# eMMC.net
KiCad netlist of a schematic drawn in Altium Designer
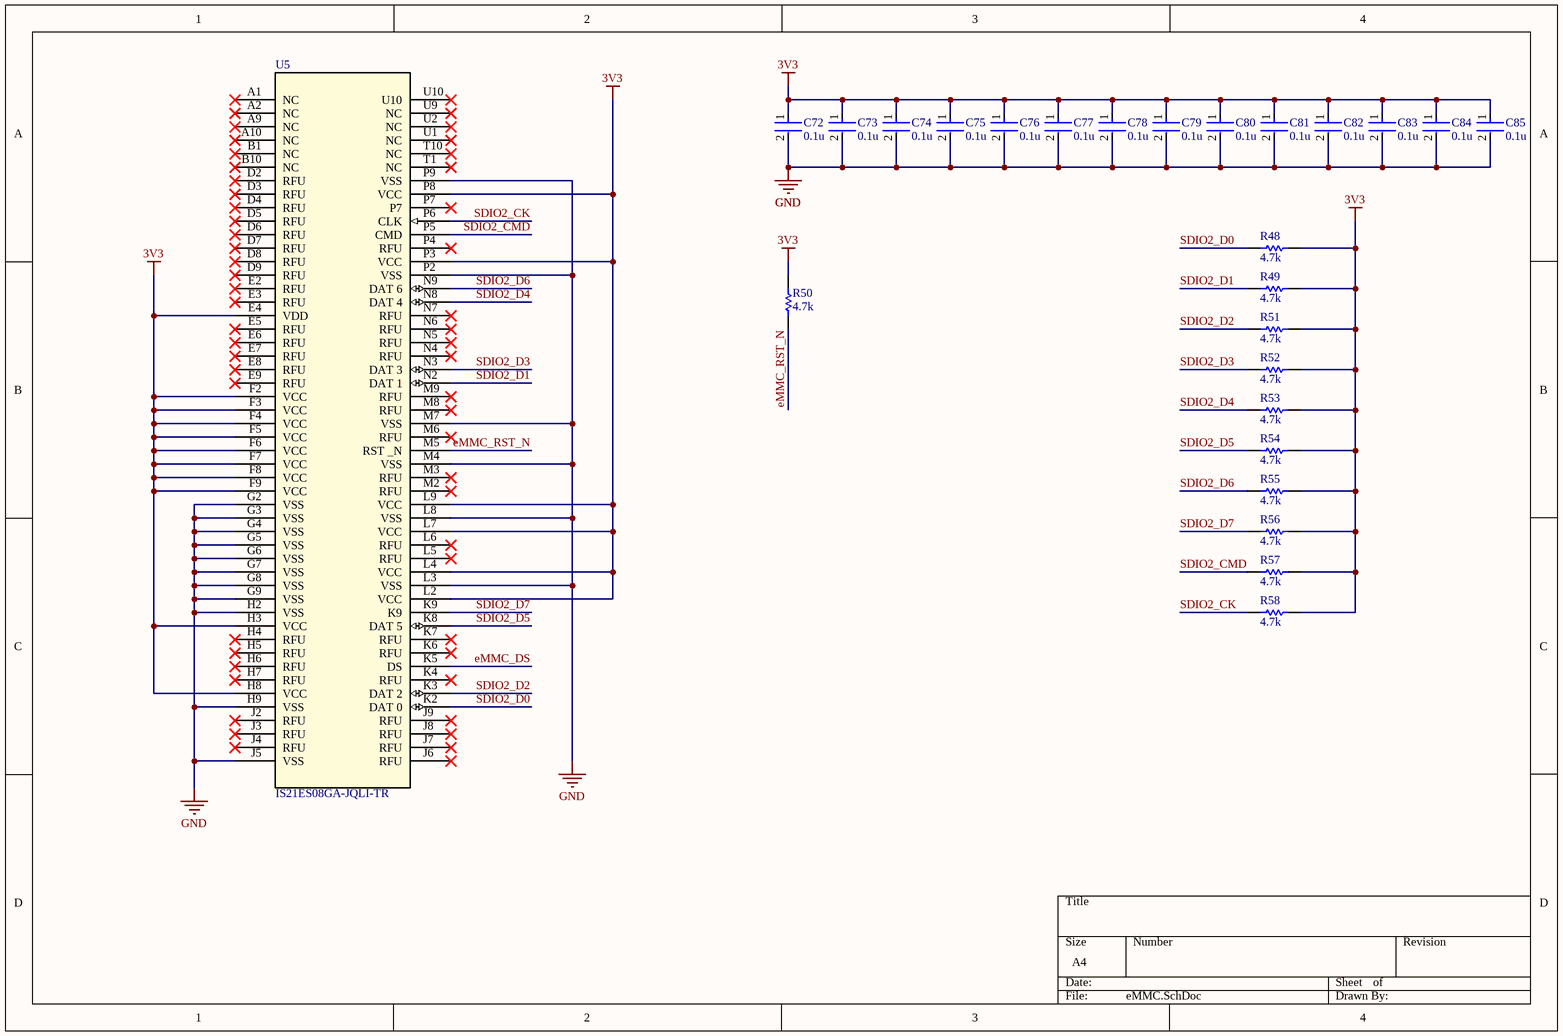
[diagram p0: eMMC.SchDoc]

(export (version "E")
  (design (tool "Eeschema 10.0.6"))
  (components
    (comp (ref "C72")
      (value "0.1u")
      (footprint "FP-C0603C-CF-MFG")
      (description "CAP CER 0.1UF 50V X7R 0603")
      (fields (field (name "TOLERANCE") "0.1") (field (name "MANUFACTURER") "KEMET"))
      (libsource (lib "Altium Content Vault") (part "b4654b650e69147ec39a6b967a45e02"))
    )
    (comp (ref "C73")
      (value "0.1u")
      (footprint "FP-C0603C-CF-MFG")
      (description "CAP CER 0.1UF 50V X7R 0603")
      (fields (field (name "TOLERANCE") "0.1") (field (name "MANUFACTURER") "KEMET"))
      (libsource (lib "Altium Content Vault") (part "b4654b650e69147ec39a6b967a45e02"))
    )
    (comp (ref "C74")
      (value "0.1u")
      (footprint "FP-C0603C-CF-MFG")
      (description "CAP CER 0.1UF 50V X7R 0603")
      (fields (field (name "TOLERANCE") "0.1") (field (name "MANUFACTURER") "KEMET"))
      (libsource (lib "Altium Content Vault") (part "b4654b650e69147ec39a6b967a45e02"))
    )
    (comp (ref "C75")
      (value "0.1u")
      (footprint "FP-C0603C-CF-MFG")
      (description "CAP CER 0.1UF 50V X7R 0603")
      (fields (field (name "TOLERANCE") "0.1") (field (name "MANUFACTURER") "KEMET"))
      (libsource (lib "Altium Content Vault") (part "b4654b650e69147ec39a6b967a45e02"))
    )
    (comp (ref "C76")
      (value "0.1u")
      (footprint "FP-C0603C-CF-MFG")
      (description "CAP CER 0.1UF 50V X7R 0603")
      (fields (field (name "TOLERANCE") "0.1") (field (name "MANUFACTURER") "KEMET"))
      (libsource (lib "Altium Content Vault") (part "b4654b650e69147ec39a6b967a45e02"))
    )
    (comp (ref "C77")
      (value "0.1u")
      (footprint "FP-C0603C-CF-MFG")
      (description "CAP CER 0.1UF 50V X7R 0603")
      (fields (field (name "TOLERANCE") "0.1") (field (name "MANUFACTURER") "KEMET"))
      (libsource (lib "Altium Content Vault") (part "b4654b650e69147ec39a6b967a45e02"))
    )
    (comp (ref "C78")
      (value "0.1u")
      (footprint "FP-C0603C-CF-MFG")
      (description "CAP CER 0.1UF 50V X7R 0603")
      (fields (field (name "TOLERANCE") "0.1") (field (name "MANUFACTURER") "KEMET"))
      (libsource (lib "Altium Content Vault") (part "b4654b650e69147ec39a6b967a45e02"))
    )
    (comp (ref "C79")
      (value "0.1u")
      (footprint "FP-C0603C-CF-MFG")
      (description "CAP CER 0.1UF 50V X7R 0603")
      (fields (field (name "TOLERANCE") "0.1") (field (name "MANUFACTURER") "KEMET"))
      (libsource (lib "Altium Content Vault") (part "b4654b650e69147ec39a6b967a45e02"))
    )
    (comp (ref "C80")
      (value "0.1u")
      (footprint "FP-C0603C-CF-MFG")
      (description "CAP CER 0.1UF 50V X7R 0603")
      (fields (field (name "TOLERANCE") "0.1") (field (name "MANUFACTURER") "KEMET"))
      (libsource (lib "Altium Content Vault") (part "b4654b650e69147ec39a6b967a45e02"))
    )
    (comp (ref "C81")
      (value "0.1u")
      (footprint "FP-C0603C-CF-MFG")
      (description "CAP CER 0.1UF 50V X7R 0603")
      (fields (field (name "TOLERANCE") "0.1") (field (name "MANUFACTURER") "KEMET"))
      (libsource (lib "Altium Content Vault") (part "b4654b650e69147ec39a6b967a45e02"))
    )
    (comp (ref "C82")
      (value "0.1u")
      (footprint "FP-C0603C-CF-MFG")
      (description "CAP CER 0.1UF 50V X7R 0603")
      (fields (field (name "TOLERANCE") "0.1") (field (name "MANUFACTURER") "KEMET"))
      (libsource (lib "Altium Content Vault") (part "b4654b650e69147ec39a6b967a45e02"))
    )
    (comp (ref "C83")
      (value "0.1u")
      (footprint "FP-C0603C-CF-MFG")
      (description "CAP CER 0.1UF 50V X7R 0603")
      (fields (field (name "TOLERANCE") "0.1") (field (name "MANUFACTURER") "KEMET"))
      (libsource (lib "Altium Content Vault") (part "b4654b650e69147ec39a6b967a45e02"))
    )
    (comp (ref "C84")
      (value "0.1u")
      (footprint "FP-C0603C-CF-MFG")
      (description "CAP CER 0.1UF 50V X7R 0603")
      (fields (field (name "TOLERANCE") "0.1") (field (name "MANUFACTURER") "KEMET"))
      (libsource (lib "Altium Content Vault") (part "b4654b650e69147ec39a6b967a45e02"))
    )
    (comp (ref "C85")
      (value "0.1u")
      (footprint "FP-C0603C-CF-MFG")
      (description "CAP CER 0.1UF 50V X7R 0603")
      (fields (field (name "TOLERANCE") "0.1") (field (name "MANUFACTURER") "KEMET"))
      (libsource (lib "Altium Content Vault") (part "b4654b650e69147ec39a6b967a45e02"))
    )
    (comp (ref "R48")
      (value "4.7k")
      (footprint "RESC1609X50X30NL8T20")
      (description "Chip Resistor, 10 KOhm, +/- 1%, 100 mW, -55 to 155 degC, 0603 (1608 Metric), RoHS, Tape and Reel")
      (fields (field (name "MANUFACTURER") "Vishay Semiconductor"))
      (libsource (lib "Altium Content Vault") (part "RES-2"))
    )
    (comp (ref "R49")
      (value "4.7k")
      (footprint "RESC1609X50X30NL8T20")
      (description "Chip Resistor, 10 KOhm, +/- 1%, 100 mW, -55 to 155 degC, 0603 (1608 Metric), RoHS, Tape and Reel")
      (fields (field (name "MANUFACTURER") "Vishay Semiconductor"))
      (libsource (lib "Altium Content Vault") (part "RES-2"))
    )
    (comp (ref "R50")
      (value "4.7k")
      (footprint "RESC1609X50X30NL8T20")
      (description "Chip Resistor, 10 KOhm, +/- 1%, 100 mW, -55 to 155 degC, 0603 (1608 Metric), RoHS, Tape and Reel")
      (fields (field (name "MANUFACTURER") "Vishay Semiconductor"))
      (libsource (lib "Altium Content Vault") (part "RES-2"))
    )
    (comp (ref "R51")
      (value "4.7k")
      (footprint "RESC1609X50X30NL8T20")
      (description "Chip Resistor, 10 KOhm, +/- 1%, 100 mW, -55 to 155 degC, 0603 (1608 Metric), RoHS, Tape and Reel")
      (fields (field (name "MANUFACTURER") "Vishay Semiconductor"))
      (libsource (lib "Altium Content Vault") (part "RES-2"))
    )
    (comp (ref "R52")
      (value "4.7k")
      (footprint "RESC1609X50X30NL8T20")
      (description "Chip Resistor, 10 KOhm, +/- 1%, 100 mW, -55 to 155 degC, 0603 (1608 Metric), RoHS, Tape and Reel")
      (fields (field (name "MANUFACTURER") "Vishay Semiconductor"))
      (libsource (lib "Altium Content Vault") (part "RES-2"))
    )
    (comp (ref "R53")
      (value "4.7k")
      (footprint "RESC1609X50X30NL8T20")
      (description "Chip Resistor, 10 KOhm, +/- 1%, 100 mW, -55 to 155 degC, 0603 (1608 Metric), RoHS, Tape and Reel")
      (fields (field (name "MANUFACTURER") "Vishay Semiconductor"))
      (libsource (lib "Altium Content Vault") (part "RES-2"))
    )
    (comp (ref "R54")
      (value "4.7k")
      (footprint "RESC1609X50X30NL8T20")
      (description "Chip Resistor, 10 KOhm, +/- 1%, 100 mW, -55 to 155 degC, 0603 (1608 Metric), RoHS, Tape and Reel")
      (fields (field (name "MANUFACTURER") "Vishay Semiconductor"))
      (libsource (lib "Altium Content Vault") (part "RES-2"))
    )
    (comp (ref "R55")
      (value "4.7k")
      (footprint "RESC1609X50X30NL8T20")
      (description "Chip Resistor, 10 KOhm, +/- 1%, 100 mW, -55 to 155 degC, 0603 (1608 Metric), RoHS, Tape and Reel")
      (fields (field (name "MANUFACTURER") "Vishay Semiconductor"))
      (libsource (lib "Altium Content Vault") (part "RES-2"))
    )
    (comp (ref "R56")
      (value "4.7k")
      (footprint "RESC1609X50X30NL8T20")
      (description "Chip Resistor, 10 KOhm, +/- 1%, 100 mW, -55 to 155 degC, 0603 (1608 Metric), RoHS, Tape and Reel")
      (fields (field (name "MANUFACTURER") "Vishay Semiconductor"))
      (libsource (lib "Altium Content Vault") (part "RES-2"))
    )
    (comp (ref "R57")
      (value "4.7k")
      (footprint "RESC1609X50X30NL8T20")
      (description "Chip Resistor, 10 KOhm, +/- 1%, 100 mW, -55 to 155 degC, 0603 (1608 Metric), RoHS, Tape and Reel")
      (fields (field (name "MANUFACTURER") "Vishay Semiconductor"))
      (libsource (lib "Altium Content Vault") (part "RES-2"))
    )
    (comp (ref "R58")
      (value "4.7k")
      (footprint "RESC1609X50X30NL8T20")
      (description "Chip Resistor, 10 KOhm, +/- 1%, 100 mW, -55 to 155 degC, 0603 (1608 Metric), RoHS, Tape and Reel")
      (fields (field (name "MANUFACTURER") "Vishay Semiconductor"))
      (libsource (lib "Altium Content Vault") (part "RES-2"))
    )
    (comp (ref "U5")
      (value "IS21ES08GA-JQLI-TR")
      (footprint "FBGA100_ISI")
      (description "No Description Available")
      (libsource (lib "Master") (part "IS21ES08GA-JQLI-TR"))
    )
  )
  (nets
    (net (code "1") (name "/SDIO2_CK") (class "Default")
      (node (ref "R58") (pin "2") (pinfunction "2_2") (pintype "passive"))
      (node (ref "U5") (pin "P6") (pinfunction "CLK_P6") (pintype "input"))
    )
    (net (code "2") (name "/SDIO2_CMD") (class "Default")
      (node (ref "R57") (pin "2") (pinfunction "2_2") (pintype "passive"))
      (node (ref "U5") (pin "P5") (pinfunction "CMD_P5") (pintype "passive"))
    )
    (net (code "3") (name "/SDIO2_D0") (class "Default")
      (node (ref "R48") (pin "2") (pinfunction "2_2") (pintype "passive"))
      (node (ref "U5") (pin "K2") (pinfunction "DAT_0_K2") (pintype "bidirectional"))
    )
    (net (code "4") (name "/SDIO2_D1") (class "Default")
      (node (ref "R49") (pin "2") (pinfunction "2_2") (pintype "passive"))
      (node (ref "U5") (pin "N2") (pinfunction "DAT_1_N2") (pintype "bidirectional"))
    )
    (net (code "5") (name "/SDIO2_D2") (class "Default")
      (node (ref "R51") (pin "2") (pinfunction "2_2") (pintype "passive"))
      (node (ref "U5") (pin "K3") (pinfunction "DAT_2_K3") (pintype "bidirectional"))
    )
    (net (code "6") (name "/SDIO2_D3") (class "Default")
      (node (ref "R52") (pin "2") (pinfunction "2_2") (pintype "passive"))
      (node (ref "U5") (pin "N3") (pinfunction "DAT_3_N3") (pintype "bidirectional"))
    )
    (net (code "7") (name "/SDIO2_D4") (class "Default")
      (node (ref "R53") (pin "2") (pinfunction "2_2") (pintype "passive"))
      (node (ref "U5") (pin "N8") (pinfunction "DAT_4_N8") (pintype "bidirectional"))
    )
    (net (code "8") (name "/SDIO2_D5") (class "Default")
      (node (ref "R54") (pin "2") (pinfunction "2_2") (pintype "passive"))
      (node (ref "U5") (pin "K8") (pinfunction "DAT_5_K8") (pintype "bidirectional"))
    )
    (net (code "9") (name "/SDIO2_D6") (class "Default")
      (node (ref "R55") (pin "2") (pinfunction "2_2") (pintype "passive"))
      (node (ref "U5") (pin "N9") (pinfunction "DAT_6_N9") (pintype "bidirectional"))
    )
    (net (code "10") (name "/SDIO2_D7") (class "Default")
      (node (ref "R56") (pin "2") (pinfunction "2_2") (pintype "passive"))
      (node (ref "U5") (pin "K9") (pinfunction "K9_K9") (pintype "passive"))
    )
    (net (code "11") (name "/eMMC_DS") (class "Default")
      (node (ref "U5") (pin "K5") (pinfunction "DS_K5") (pintype "passive"))
    )
    (net (code "12") (name "/eMMC_RST_N") (class "Default")
      (node (ref "R50") (pin "1") (pinfunction "1_1") (pintype "passive"))
      (node (ref "U5") (pin "M5") (pinfunction "RST__N_M5") (pintype "passive"))
    )
    (net (code "13") (name "3V3") (class "Default")
      (node (ref "C72") (pin "1") (pinfunction "1_1") (pintype "passive"))
      (node (ref "C73") (pin "1") (pinfunction "1_1") (pintype "passive"))
      (node (ref "C74") (pin "1") (pinfunction "1_1") (pintype "passive"))
      (node (ref "C75") (pin "1") (pinfunction "1_1") (pintype "passive"))
      (node (ref "C76") (pin "1") (pinfunction "1_1") (pintype "passive"))
      (node (ref "C77") (pin "1") (pinfunction "1_1") (pintype "passive"))
      (node (ref "C78") (pin "1") (pinfunction "1_1") (pintype "passive"))
      (node (ref "C79") (pin "1") (pinfunction "1_1") (pintype "passive"))
      (node (ref "C80") (pin "1") (pinfunction "1_1") (pintype "passive"))
      (node (ref "C81") (pin "1") (pinfunction "1_1") (pintype "passive"))
      (node (ref "C82") (pin "1") (pinfunction "1_1") (pintype "passive"))
      (node (ref "C83") (pin "1") (pinfunction "1_1") (pintype "passive"))
      (node (ref "C84") (pin "1") (pinfunction "1_1") (pintype "passive"))
      (node (ref "C85") (pin "1") (pinfunction "1_1") (pintype "passive"))
      (node (ref "R48") (pin "1") (pinfunction "1_1") (pintype "passive"))
      (node (ref "R49") (pin "1") (pinfunction "1_1") (pintype "passive"))
      (node (ref "R50") (pin "2") (pinfunction "2_2") (pintype "passive"))
      (node (ref "R51") (pin "1") (pinfunction "1_1") (pintype "passive"))
      (node (ref "R52") (pin "1") (pinfunction "1_1") (pintype "passive"))
      (node (ref "R53") (pin "1") (pinfunction "1_1") (pintype "passive"))
      (node (ref "R54") (pin "1") (pinfunction "1_1") (pintype "passive"))
      (node (ref "R55") (pin "1") (pinfunction "1_1") (pintype "passive"))
      (node (ref "R56") (pin "1") (pinfunction "1_1") (pintype "passive"))
      (node (ref "R57") (pin "1") (pinfunction "1_1") (pintype "passive"))
      (node (ref "R58") (pin "1") (pinfunction "1_1") (pintype "passive"))
      (node (ref "U5") (pin "E4") (pinfunction "VDD_E4") (pintype "power_in"))
      (node (ref "U5") (pin "F2") (pinfunction "VCC_F2") (pintype "power_in"))
      (node (ref "U5") (pin "F3") (pinfunction "VCC_F3") (pintype "power_in"))
      (node (ref "U5") (pin "F4") (pinfunction "VCC_F4") (pintype "power_in"))
      (node (ref "U5") (pin "F5") (pinfunction "VCC_F5") (pintype "power_in"))
      (node (ref "U5") (pin "F6") (pinfunction "VCC_F6") (pintype "power_in"))
      (node (ref "U5") (pin "F7") (pinfunction "VCC_F7") (pintype "power_in"))
      (node (ref "U5") (pin "F8") (pinfunction "VCC_F8") (pintype "power_in"))
      (node (ref "U5") (pin "F9") (pinfunction "VCC_F9") (pintype "power_in"))
      (node (ref "U5") (pin "H3") (pinfunction "VCC_H3") (pintype "power_in"))
      (node (ref "U5") (pin "H8") (pinfunction "VCC_H8") (pintype "power_in"))
      (node (ref "U5") (pin "L2") (pinfunction "VCC_L2") (pintype "power_in"))
      (node (ref "U5") (pin "L4") (pinfunction "VCC_L4") (pintype "power_in"))
      (node (ref "U5") (pin "L7") (pinfunction "VCC_L7") (pintype "power_in"))
      (node (ref "U5") (pin "L9") (pinfunction "VCC_L9") (pintype "power_in"))
      (node (ref "U5") (pin "P3") (pinfunction "VCC_P3") (pintype "power_in"))
      (node (ref "U5") (pin "P8") (pinfunction "VCC_P8") (pintype "power_in"))
    )
    (net (code "14") (name "GND") (class "Default")
      (node (ref "C72") (pin "2") (pinfunction "2_2") (pintype "passive"))
      (node (ref "C73") (pin "2") (pinfunction "2_2") (pintype "passive"))
      (node (ref "C74") (pin "2") (pinfunction "2_2") (pintype "passive"))
      (node (ref "C75") (pin "2") (pinfunction "2_2") (pintype "passive"))
      (node (ref "C76") (pin "2") (pinfunction "2_2") (pintype "passive"))
      (node (ref "C77") (pin "2") (pinfunction "2_2") (pintype "passive"))
      (node (ref "C78") (pin "2") (pinfunction "2_2") (pintype "passive"))
      (node (ref "C79") (pin "2") (pinfunction "2_2") (pintype "passive"))
      (node (ref "C80") (pin "2") (pinfunction "2_2") (pintype "passive"))
      (node (ref "C81") (pin "2") (pinfunction "2_2") (pintype "passive"))
      (node (ref "C82") (pin "2") (pinfunction "2_2") (pintype "passive"))
      (node (ref "C83") (pin "2") (pinfunction "2_2") (pintype "passive"))
      (node (ref "C84") (pin "2") (pinfunction "2_2") (pintype "passive"))
      (node (ref "C85") (pin "2") (pinfunction "2_2") (pintype "passive"))
      (node (ref "U5") (pin "G2") (pinfunction "VSS_G2") (pintype "power_in"))
      (node (ref "U5") (pin "G3") (pinfunction "VSS_G3") (pintype "power_in"))
      (node (ref "U5") (pin "G4") (pinfunction "VSS_G4") (pintype "power_in"))
      (node (ref "U5") (pin "G5") (pinfunction "VSS_G5") (pintype "power_in"))
      (node (ref "U5") (pin "G6") (pinfunction "VSS_G6") (pintype "power_in"))
      (node (ref "U5") (pin "G7") (pinfunction "VSS_G7") (pintype "power_in"))
      (node (ref "U5") (pin "G8") (pinfunction "VSS_G8") (pintype "power_in"))
      (node (ref "U5") (pin "G9") (pinfunction "VSS_G9") (pintype "power_in"))
      (node (ref "U5") (pin "H2") (pinfunction "VSS_H2") (pintype "power_in"))
      (node (ref "U5") (pin "H9") (pinfunction "VSS_H9") (pintype "power_in"))
      (node (ref "U5") (pin "J5") (pinfunction "VSS_J5") (pintype "power_in"))
      (node (ref "U5") (pin "L3") (pinfunction "VSS_L3") (pintype "power_in"))
      (node (ref "U5") (pin "L8") (pinfunction "VSS_L8") (pintype "power_in"))
      (node (ref "U5") (pin "M4") (pinfunction "VSS_M4") (pintype "power_in"))
      (node (ref "U5") (pin "M7") (pinfunction "VSS_M7") (pintype "power_in"))
      (node (ref "U5") (pin "P2") (pinfunction "VSS_P2") (pintype "power_in"))
      (node (ref "U5") (pin "P9") (pinfunction "VSS_P9") (pintype "power_in"))
    )
    (net (code "15") (name "unconnected-(U5-NC-PadA1)") (class "Default")
      (node (ref "U5") (pin "A1") (pinfunction "NC_A1") (pintype "passive+no_connect"))
    )
    (net (code "16") (name "unconnected-(U5-NC-PadA2)") (class "Default")
      (node (ref "U5") (pin "A2") (pinfunction "NC_A2") (pintype "passive+no_connect"))
    )
    (net (code "17") (name "unconnected-(U5-NC-PadA9)") (class "Default")
      (node (ref "U5") (pin "A9") (pinfunction "NC_A9") (pintype "passive+no_connect"))
    )
    (net (code "18") (name "unconnected-(U5-NC-PadA10)") (class "Default")
      (node (ref "U5") (pin "A10") (pinfunction "NC_A10") (pintype "passive+no_connect"))
    )
    (net (code "19") (name "unconnected-(U5-NC-PadB1)") (class "Default")
      (node (ref "U5") (pin "B1") (pinfunction "NC_B1") (pintype "passive+no_connect"))
    )
    (net (code "20") (name "unconnected-(U5-NC-PadB10)") (class "Default")
      (node (ref "U5") (pin "B10") (pinfunction "NC_B10") (pintype "passive+no_connect"))
    )
    (net (code "21") (name "unconnected-(U5-NC-PadT1)") (class "Default")
      (node (ref "U5") (pin "T1") (pinfunction "NC_T1") (pintype "passive+no_connect"))
    )
    (net (code "22") (name "unconnected-(U5-NC-PadT10)") (class "Default")
      (node (ref "U5") (pin "T10") (pinfunction "NC_T10") (pintype "passive+no_connect"))
    )
    (net (code "23") (name "unconnected-(U5-NC-PadU1)") (class "Default")
      (node (ref "U5") (pin "U1") (pinfunction "NC_U1") (pintype "passive+no_connect"))
    )
    (net (code "24") (name "unconnected-(U5-NC-PadU2)") (class "Default")
      (node (ref "U5") (pin "U2") (pinfunction "NC_U2") (pintype "passive+no_connect"))
    )
    (net (code "25") (name "unconnected-(U5-NC-PadU9)") (class "Default")
      (node (ref "U5") (pin "U9") (pinfunction "NC_U9") (pintype "passive+no_connect"))
    )
    (net (code "26") (name "unconnected-(U5-PadP7)") (class "Default")
      (node (ref "U5") (pin "P7") (pinfunction "P7_P7") (pintype "passive+no_connect"))
    )
    (net (code "27") (name "unconnected-(U5-PadU10)") (class "Default")
      (node (ref "U5") (pin "U10") (pinfunction "U10_U10") (pintype "passive+no_connect"))
    )
    (net (code "28") (name "unconnected-(U5-RFU-PadD2)") (class "Default")
      (node (ref "U5") (pin "D2") (pinfunction "RFU_D2") (pintype "passive+no_connect"))
    )
    (net (code "29") (name "unconnected-(U5-RFU-PadD3)") (class "Default")
      (node (ref "U5") (pin "D3") (pinfunction "RFU_D3") (pintype "passive+no_connect"))
    )
    (net (code "30") (name "unconnected-(U5-RFU-PadD4)") (class "Default")
      (node (ref "U5") (pin "D4") (pinfunction "RFU_D4") (pintype "passive+no_connect"))
    )
    (net (code "31") (name "unconnected-(U5-RFU-PadD5)") (class "Default")
      (node (ref "U5") (pin "D5") (pinfunction "RFU_D5") (pintype "passive+no_connect"))
    )
    (net (code "32") (name "unconnected-(U5-RFU-PadD6)") (class "Default")
      (node (ref "U5") (pin "D6") (pinfunction "RFU_D6") (pintype "passive+no_connect"))
    )
    (net (code "33") (name "unconnected-(U5-RFU-PadD7)") (class "Default")
      (node (ref "U5") (pin "D7") (pinfunction "RFU_D7") (pintype "passive+no_connect"))
    )
    (net (code "34") (name "unconnected-(U5-RFU-PadD8)") (class "Default")
      (node (ref "U5") (pin "D8") (pinfunction "RFU_D8") (pintype "passive+no_connect"))
    )
    (net (code "35") (name "unconnected-(U5-RFU-PadD9)") (class "Default")
      (node (ref "U5") (pin "D9") (pinfunction "RFU_D9") (pintype "passive+no_connect"))
    )
    (net (code "36") (name "unconnected-(U5-RFU-PadE2)") (class "Default")
      (node (ref "U5") (pin "E2") (pinfunction "RFU_E2") (pintype "passive+no_connect"))
    )
    (net (code "37") (name "unconnected-(U5-RFU-PadE3)") (class "Default")
      (node (ref "U5") (pin "E3") (pinfunction "RFU_E3") (pintype "passive+no_connect"))
    )
    (net (code "38") (name "unconnected-(U5-RFU-PadE5)") (class "Default")
      (node (ref "U5") (pin "E5") (pinfunction "RFU_E5") (pintype "passive+no_connect"))
    )
    (net (code "39") (name "unconnected-(U5-RFU-PadE6)") (class "Default")
      (node (ref "U5") (pin "E6") (pinfunction "RFU_E6") (pintype "passive+no_connect"))
    )
    (net (code "40") (name "unconnected-(U5-RFU-PadE7)") (class "Default")
      (node (ref "U5") (pin "E7") (pinfunction "RFU_E7") (pintype "passive+no_connect"))
    )
    (net (code "41") (name "unconnected-(U5-RFU-PadE8)") (class "Default")
      (node (ref "U5") (pin "E8") (pinfunction "RFU_E8") (pintype "passive+no_connect"))
    )
    (net (code "42") (name "unconnected-(U5-RFU-PadE9)") (class "Default")
      (node (ref "U5") (pin "E9") (pinfunction "RFU_E9") (pintype "passive+no_connect"))
    )
    (net (code "43") (name "unconnected-(U5-RFU-PadH4)") (class "Default")
      (node (ref "U5") (pin "H4") (pinfunction "RFU_H4") (pintype "passive+no_connect"))
    )
    (net (code "44") (name "unconnected-(U5-RFU-PadH5)") (class "Default")
      (node (ref "U5") (pin "H5") (pinfunction "RFU_H5") (pintype "passive+no_connect"))
    )
    (net (code "45") (name "unconnected-(U5-RFU-PadH6)") (class "Default")
      (node (ref "U5") (pin "H6") (pinfunction "RFU_H6") (pintype "passive+no_connect"))
    )
    (net (code "46") (name "unconnected-(U5-RFU-PadH7)") (class "Default")
      (node (ref "U5") (pin "H7") (pinfunction "RFU_H7") (pintype "passive+no_connect"))
    )
    (net (code "47") (name "unconnected-(U5-RFU-PadJ2)") (class "Default")
      (node (ref "U5") (pin "J2") (pinfunction "RFU_J2") (pintype "passive+no_connect"))
    )
    (net (code "48") (name "unconnected-(U5-RFU-PadJ3)") (class "Default")
      (node (ref "U5") (pin "J3") (pinfunction "RFU_J3") (pintype "passive+no_connect"))
    )
    (net (code "49") (name "unconnected-(U5-RFU-PadJ4)") (class "Default")
      (node (ref "U5") (pin "J4") (pinfunction "RFU_J4") (pintype "passive+no_connect"))
    )
    (net (code "50") (name "unconnected-(U5-RFU-PadJ6)") (class "Default")
      (node (ref "U5") (pin "J6") (pinfunction "RFU_J6") (pintype "passive+no_connect"))
    )
    (net (code "51") (name "unconnected-(U5-RFU-PadJ7)") (class "Default")
      (node (ref "U5") (pin "J7") (pinfunction "RFU_J7") (pintype "passive+no_connect"))
    )
    (net (code "52") (name "unconnected-(U5-RFU-PadJ8)") (class "Default")
      (node (ref "U5") (pin "J8") (pinfunction "RFU_J8") (pintype "passive+no_connect"))
    )
    (net (code "53") (name "unconnected-(U5-RFU-PadJ9)") (class "Default")
      (node (ref "U5") (pin "J9") (pinfunction "RFU_J9") (pintype "passive+no_connect"))
    )
    (net (code "54") (name "unconnected-(U5-RFU-PadK4)") (class "Default")
      (node (ref "U5") (pin "K4") (pinfunction "RFU_K4") (pintype "passive+no_connect"))
    )
    (net (code "55") (name "unconnected-(U5-RFU-PadK6)") (class "Default")
      (node (ref "U5") (pin "K6") (pinfunction "RFU_K6") (pintype "passive+no_connect"))
    )
    (net (code "56") (name "unconnected-(U5-RFU-PadK7)") (class "Default")
      (node (ref "U5") (pin "K7") (pinfunction "RFU_K7") (pintype "passive+no_connect"))
    )
    (net (code "57") (name "unconnected-(U5-RFU-PadL5)") (class "Default")
      (node (ref "U5") (pin "L5") (pinfunction "RFU_L5") (pintype "passive+no_connect"))
    )
    (net (code "58") (name "unconnected-(U5-RFU-PadL6)") (class "Default")
      (node (ref "U5") (pin "L6") (pinfunction "RFU_L6") (pintype "passive+no_connect"))
    )
    (net (code "59") (name "unconnected-(U5-RFU-PadM2)") (class "Default")
      (node (ref "U5") (pin "M2") (pinfunction "RFU_M2") (pintype "passive+no_connect"))
    )
    (net (code "60") (name "unconnected-(U5-RFU-PadM3)") (class "Default")
      (node (ref "U5") (pin "M3") (pinfunction "RFU_M3") (pintype "passive+no_connect"))
    )
    (net (code "61") (name "unconnected-(U5-RFU-PadM6)") (class "Default")
      (node (ref "U5") (pin "M6") (pinfunction "RFU_M6") (pintype "passive+no_connect"))
    )
    (net (code "62") (name "unconnected-(U5-RFU-PadM8)") (class "Default")
      (node (ref "U5") (pin "M8") (pinfunction "RFU_M8") (pintype "passive+no_connect"))
    )
    (net (code "63") (name "unconnected-(U5-RFU-PadM9)") (class "Default")
      (node (ref "U5") (pin "M9") (pinfunction "RFU_M9") (pintype "passive+no_connect"))
    )
    (net (code "64") (name "unconnected-(U5-RFU-PadN4)") (class "Default")
      (node (ref "U5") (pin "N4") (pinfunction "RFU_N4") (pintype "passive+no_connect"))
    )
    (net (code "65") (name "unconnected-(U5-RFU-PadN5)") (class "Default")
      (node (ref "U5") (pin "N5") (pinfunction "RFU_N5") (pintype "passive+no_connect"))
    )
    (net (code "66") (name "unconnected-(U5-RFU-PadN6)") (class "Default")
      (node (ref "U5") (pin "N6") (pinfunction "RFU_N6") (pintype "passive+no_connect"))
    )
    (net (code "67") (name "unconnected-(U5-RFU-PadN7)") (class "Default")
      (node (ref "U5") (pin "N7") (pinfunction "RFU_N7") (pintype "passive+no_connect"))
    )
    (net (code "68") (name "unconnected-(U5-RFU-PadP4)") (class "Default")
      (node (ref "U5") (pin "P4") (pinfunction "RFU_P4") (pintype "passive+no_connect"))
    )
  )
)
